# ioboard.net
KiCad netlist of a schematic drawn in EAGLE
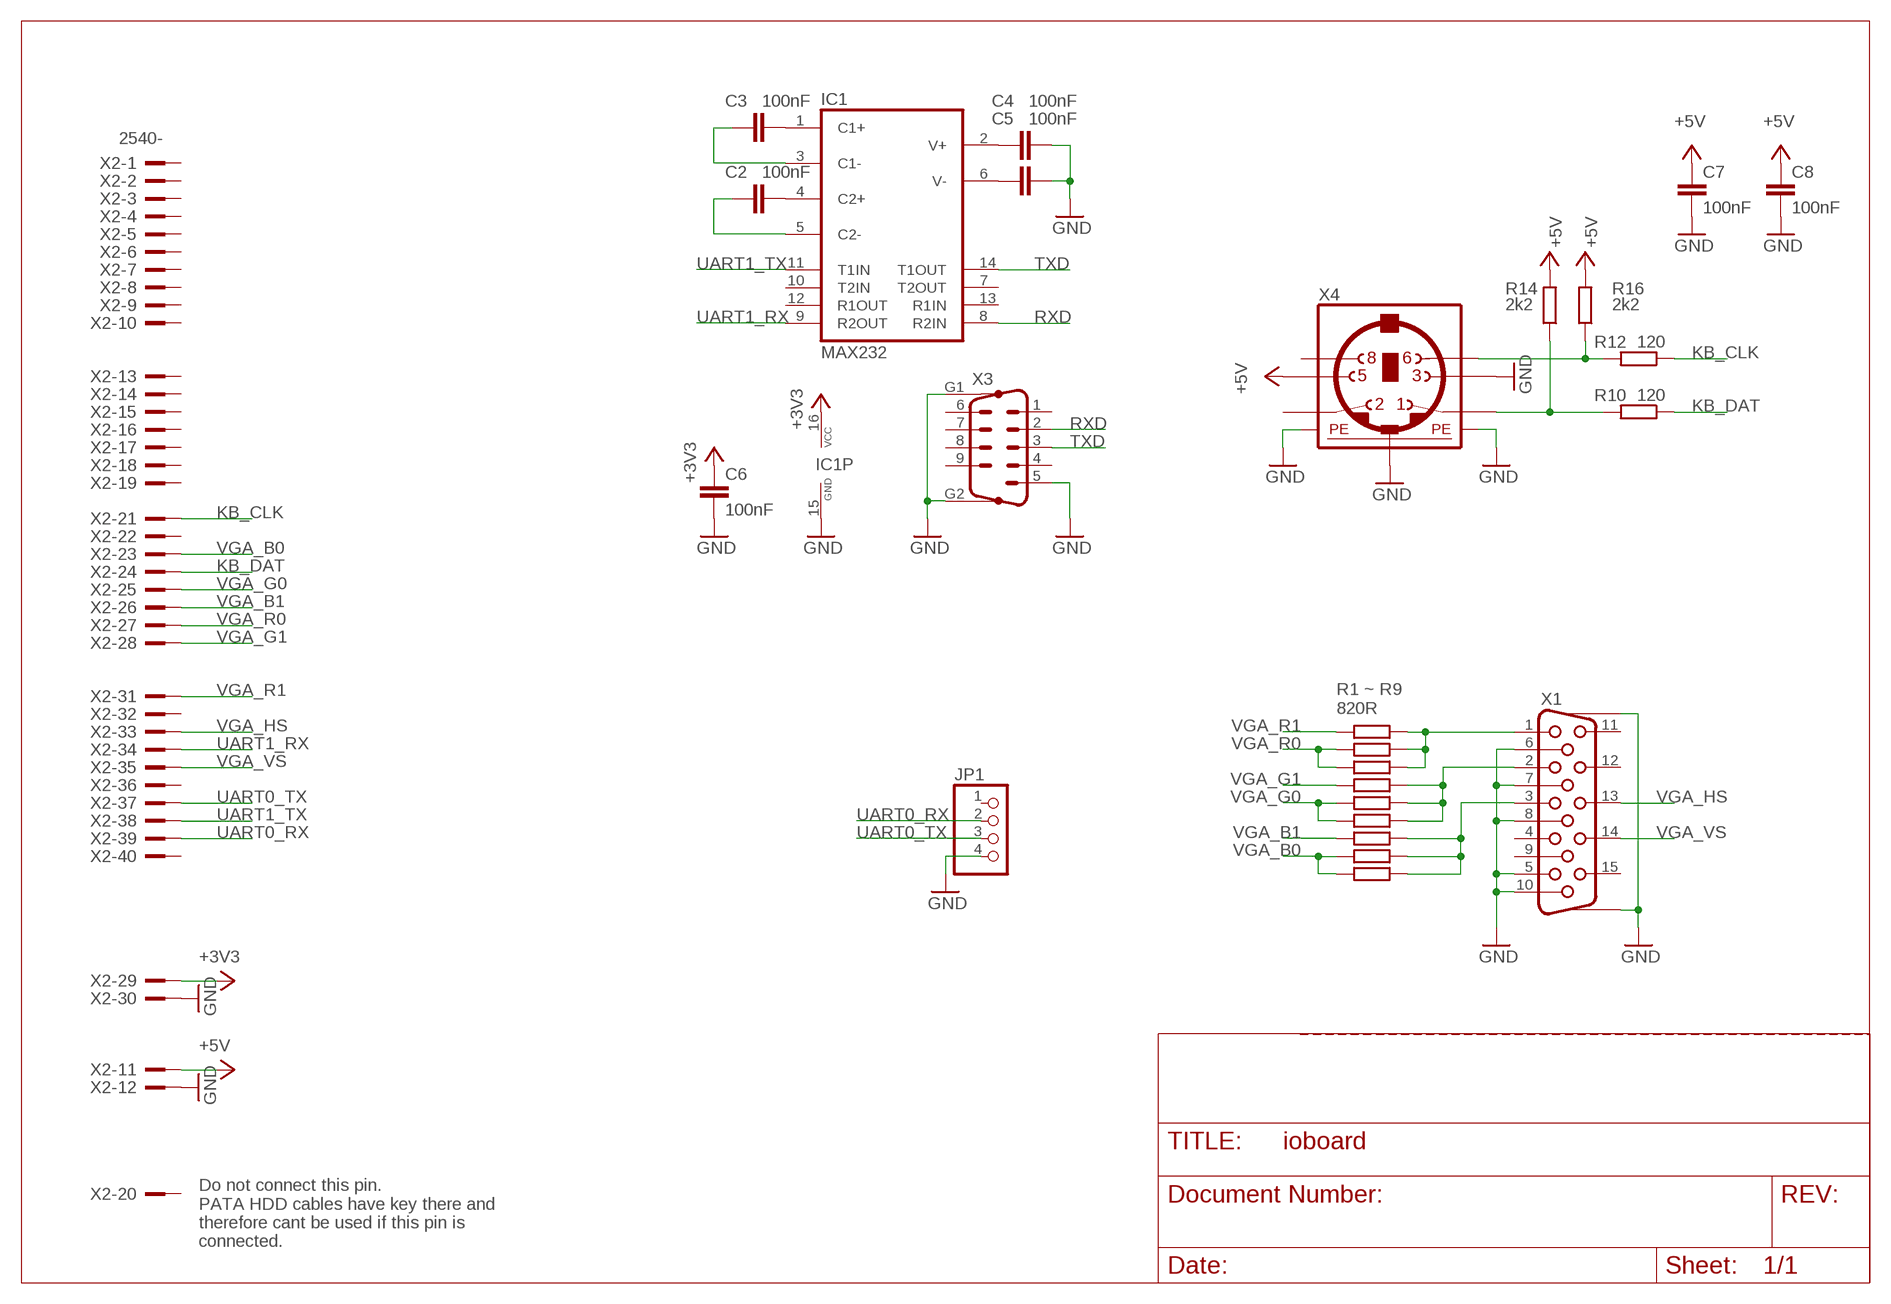
[diagram p0: schematic, sheet 1]

(export (version "E")
  (design (tool "Eeschema 10.0.6"))
  (components
    (comp (ref "C2")
      (value "100nF")
      (footprint "eagle-import:C025-025X050")
      (libsource (lib "eagle-import") (part "C-EU025-025X050"))
    )
    (comp (ref "C3")
      (value "100nF")
      (footprint "eagle-import:C025-025X050")
      (libsource (lib "eagle-import") (part "C-EU025-025X050"))
    )
    (comp (ref "C4")
      (value "100nF")
      (footprint "eagle-import:C025-025X050")
      (libsource (lib "eagle-import") (part "C-EU025-025X050"))
    )
    (comp (ref "C5")
      (value "100nF")
      (footprint "eagle-import:C025-025X050")
      (libsource (lib "eagle-import") (part "C-EU025-025X050"))
    )
    (comp (ref "C6")
      (value "100nF")
      (footprint "eagle-import:C025-025X050")
      (libsource (lib "eagle-import") (part "C-EU025-025X050"))
    )
    (comp (ref "C7")
      (value "100nF")
      (footprint "eagle-import:C025-025X050")
      (libsource (lib "eagle-import") (part "C-EU025-025X050"))
    )
    (comp (ref "C8")
      (value "100nF")
      (footprint "eagle-import:C025-025X050")
      (libsource (lib "eagle-import") (part "C-EU025-025X050"))
    )
    (comp (ref "IC1")
      (value "MAX232")
      (footprint "eagle-import:DIL16")
      (fields (field (name "MF") "MAXIM") (field (name "MPN") "MAX232ACPE+"))
      (libsource (lib "eagle-import") (part "MAX232"))
    )
    (comp (ref "JP1")
      (value "PINHD-1X4")
      (footprint "eagle-import:1X04")
      (libsource (lib "eagle-import") (part "PINHD-1X4"))
    )
    (comp (ref "R1")
      (value "820")
      (footprint "eagle-import:0204_7")
      (libsource (lib "eagle-import") (part "R-EU_0204/7"))
    )
    (comp (ref "R2")
      (value "820")
      (footprint "eagle-import:0204_7")
      (libsource (lib "eagle-import") (part "R-EU_0204/7"))
    )
    (comp (ref "R3")
      (value "820")
      (footprint "eagle-import:0204_7")
      (libsource (lib "eagle-import") (part "R-EU_0204/7"))
    )
    (comp (ref "R4")
      (value "820")
      (footprint "eagle-import:0204_7")
      (libsource (lib "eagle-import") (part "R-EU_0204/7"))
    )
    (comp (ref "R5")
      (value "820")
      (footprint "eagle-import:0204_7")
      (libsource (lib "eagle-import") (part "R-EU_0204/7"))
    )
    (comp (ref "R6")
      (value "820")
      (footprint "eagle-import:0204_7")
      (libsource (lib "eagle-import") (part "R-EU_0204/7"))
    )
    (comp (ref "R7")
      (value "820")
      (footprint "eagle-import:0204_7")
      (libsource (lib "eagle-import") (part "R-EU_0204/7"))
    )
    (comp (ref "R8")
      (value "820")
      (footprint "eagle-import:0204_7")
      (libsource (lib "eagle-import") (part "R-EU_0204/7"))
    )
    (comp (ref "R9")
      (value "820")
      (footprint "eagle-import:0204_7")
      (libsource (lib "eagle-import") (part "R-EU_0204/7"))
    )
    (comp (ref "R10")
      (value "120")
      (footprint "eagle-import:0204_7")
      (libsource (lib "eagle-import") (part "R-EU_0204/7"))
    )
    (comp (ref "R12")
      (value "120")
      (footprint "eagle-import:0204_7")
      (libsource (lib "eagle-import") (part "R-EU_0204/7"))
    )
    (comp (ref "R14")
      (value "2k2")
      (footprint "eagle-import:0204_7")
      (libsource (lib "eagle-import") (part "R-EU_0204/7"))
    )
    (comp (ref "R16")
      (value "2k2")
      (footprint "eagle-import:0204_7")
      (libsource (lib "eagle-import") (part "R-EU_0204/7"))
    )
    (comp (ref "X1")
      (value "HF15H")
      (footprint "eagle-import:HDF15H")
      (libsource (lib "eagle-import") (part "HF15H"))
    )
    (comp (ref "X2")
      (value "2540-")
      (footprint "eagle-import:PAK100_2500-40")
      (libsource (lib "eagle-import") (part "2540-"))
    )
    (comp (ref "X3")
      (value "M09HP")
      (footprint "eagle-import:M09HP")
      (libsource (lib "eagle-import") (part "M09HP"))
    )
    (comp (ref "X4")
      (value "MINI_DIN_6")
      (footprint "eagle-import:M_DIN6")
      (libsource (lib "eagle-import") (part "MINI_DIN_6"))
    )
  )
  (nets
    (net (code "1") (name "+3V3") (class "Default")
      (node (ref "C6") (pin "1") (pinfunction "1_1") (pintype "passive"))
      (node (ref "IC1") (pin "16") (pinfunction "VCC_16") (pintype "power_in"))
      (node (ref "X2") (pin "29") (pinfunction "KL_29") (pintype "passive"))
    )
    (net (code "2") (name "+5V") (class "Default")
      (node (ref "C7") (pin "1") (pinfunction "1_1") (pintype "passive"))
      (node (ref "C8") (pin "1") (pinfunction "1_1") (pintype "passive"))
      (node (ref "R14") (pin "2") (pinfunction "2_2") (pintype "passive"))
      (node (ref "R16") (pin "2") (pinfunction "2_2") (pintype "passive"))
      (node (ref "X2") (pin "11") (pinfunction "KL_11") (pintype "passive"))
      (node (ref "X4") (pin "5") (pinfunction "5_5") (pintype "passive"))
    )
    (net (code "3") (name "/KB_CLK") (class "Default")
      (node (ref "R12") (pin "1") (pinfunction "1_1") (pintype "passive"))
      (node (ref "X2") (pin "21") (pinfunction "KL_21") (pintype "passive"))
    )
    (net (code "4") (name "/KB_DAT") (class "Default")
      (node (ref "R10") (pin "1") (pinfunction "1_1") (pintype "passive"))
      (node (ref "X2") (pin "24") (pinfunction "KL_24") (pintype "passive"))
    )
    (net (code "5") (name "/RXD") (class "Default")
      (node (ref "IC1") (pin "8") (pinfunction "R2IN_8") (pintype "input"))
      (node (ref "X3") (pin "2") (pinfunction "2_2") (pintype "passive"))
    )
    (net (code "6") (name "/TXD") (class "Default")
      (node (ref "IC1") (pin "14") (pinfunction "T1OUT_14") (pintype "output"))
      (node (ref "X3") (pin "3") (pinfunction "3_3") (pintype "passive"))
    )
    (net (code "7") (name "/UART0_RX") (class "Default")
      (node (ref "JP1") (pin "2") (pinfunction "2_2") (pintype "passive"))
      (node (ref "X2") (pin "39") (pinfunction "KL_39") (pintype "passive"))
    )
    (net (code "8") (name "/UART0_TX") (class "Default")
      (node (ref "JP1") (pin "3") (pinfunction "3_3") (pintype "passive"))
      (node (ref "X2") (pin "37") (pinfunction "KL_37") (pintype "passive"))
    )
    (net (code "9") (name "/UART1_RX") (class "Default")
      (node (ref "IC1") (pin "9") (pinfunction "R2OUT_9") (pintype "output"))
      (node (ref "X2") (pin "34") (pinfunction "KL_34") (pintype "passive"))
    )
    (net (code "10") (name "/UART1_TX") (class "Default")
      (node (ref "IC1") (pin "11") (pinfunction "T1IN_11") (pintype "input"))
      (node (ref "X2") (pin "38") (pinfunction "KL_38") (pintype "passive"))
    )
    (net (code "11") (name "/VGA_B0") (class "Default")
      (node (ref "R8") (pin "2") (pinfunction "2_2") (pintype "passive"))
      (node (ref "R9") (pin "2") (pinfunction "2_2") (pintype "passive"))
      (node (ref "X2") (pin "23") (pinfunction "KL_23") (pintype "passive"))
    )
    (net (code "12") (name "/VGA_B1") (class "Default")
      (node (ref "R7") (pin "2") (pinfunction "2_2") (pintype "passive"))
      (node (ref "X2") (pin "26") (pinfunction "KL_26") (pintype "passive"))
    )
    (net (code "13") (name "/VGA_G0") (class "Default")
      (node (ref "R5") (pin "2") (pinfunction "2_2") (pintype "passive"))
      (node (ref "R6") (pin "2") (pinfunction "2_2") (pintype "passive"))
      (node (ref "X2") (pin "25") (pinfunction "KL_25") (pintype "passive"))
    )
    (net (code "14") (name "/VGA_G1") (class "Default")
      (node (ref "R4") (pin "2") (pinfunction "2_2") (pintype "passive"))
      (node (ref "X2") (pin "28") (pinfunction "KL_28") (pintype "passive"))
    )
    (net (code "15") (name "/VGA_HS") (class "Default")
      (node (ref "X1") (pin "13") (pinfunction "13_13") (pintype "passive"))
      (node (ref "X2") (pin "33") (pinfunction "KL_33") (pintype "passive"))
    )
    (net (code "16") (name "/VGA_R0") (class "Default")
      (node (ref "R2") (pin "2") (pinfunction "2_2") (pintype "passive"))
      (node (ref "R3") (pin "2") (pinfunction "2_2") (pintype "passive"))
      (node (ref "X2") (pin "27") (pinfunction "KL_27") (pintype "passive"))
    )
    (net (code "17") (name "/VGA_R1") (class "Default")
      (node (ref "R1") (pin "2") (pinfunction "2_2") (pintype "passive"))
      (node (ref "X2") (pin "31") (pinfunction "KL_31") (pintype "passive"))
    )
    (net (code "18") (name "/VGA_VS") (class "Default")
      (node (ref "X1") (pin "14") (pinfunction "14_14") (pintype "passive"))
      (node (ref "X2") (pin "35") (pinfunction "KL_35") (pintype "passive"))
    )
    (net (code "19") (name "GND") (class "Default")
      (node (ref "C4") (pin "2") (pinfunction "2_2") (pintype "passive"))
      (node (ref "C5") (pin "2") (pinfunction "2_2") (pintype "passive"))
      (node (ref "C6") (pin "2") (pinfunction "2_2") (pintype "passive"))
      (node (ref "C7") (pin "2") (pinfunction "2_2") (pintype "passive"))
      (node (ref "C8") (pin "2") (pinfunction "2_2") (pintype "passive"))
      (node (ref "IC1") (pin "15") (pinfunction "GND_15") (pintype "power_in"))
      (node (ref "JP1") (pin "4") (pinfunction "4_4") (pintype "passive"))
      (node (ref "X1") (pin "10") (pinfunction "10_10") (pintype "passive"))
      (node (ref "X1") (pin "5") (pinfunction "5_5") (pintype "passive"))
      (node (ref "X1") (pin "6") (pinfunction "6_6") (pintype "passive"))
      (node (ref "X1") (pin "7") (pinfunction "7_7") (pintype "passive"))
      (node (ref "X1") (pin "8") (pinfunction "8_8") (pintype "passive"))
      (node (ref "X1") (pin "SCH1") (pinfunction "P$1_SCH1") (pintype "passive"))
      (node (ref "X1") (pin "SCH2") (pinfunction "P$2_SCH2") (pintype "passive"))
      (node (ref "X2") (pin "12") (pinfunction "KL_12") (pintype "passive"))
      (node (ref "X2") (pin "30") (pinfunction "KL_30") (pintype "passive"))
      (node (ref "X3") (pin "5") (pinfunction "5_5") (pintype "passive"))
      (node (ref "X3") (pin "G1") (pinfunction "G1_G1") (pintype "passive"))
      (node (ref "X3") (pin "G2") (pinfunction "G2_G2") (pintype "passive"))
      (node (ref "X4") (pin "3") (pinfunction "3_3") (pintype "passive"))
      (node (ref "X4") (pin "SH1") (pinfunction "PE1_SH1") (pintype "power_in"))
      (node (ref "X4") (pin "SH2") (pinfunction "PE2_SH2") (pintype "power_in"))
      (node (ref "X4") (pin "SH3") (pinfunction "PE3_SH3") (pintype "power_in"))
    )
    (net (code "20") (name "Net-(IC1A-C1+)") (class "Default")
      (node (ref "C3") (pin "2") (pinfunction "2_2") (pintype "passive"))
      (node (ref "IC1") (pin "1") (pinfunction "C1+_1") (pintype "bidirectional"))
    )
    (net (code "21") (name "Net-(IC1A-C1-)") (class "Default")
      (node (ref "C3") (pin "1") (pinfunction "1_1") (pintype "passive"))
      (node (ref "IC1") (pin "3") (pinfunction "C1-_3") (pintype "bidirectional"))
    )
    (net (code "22") (name "Net-(IC1A-C2+)") (class "Default")
      (node (ref "C2") (pin "2") (pinfunction "2_2") (pintype "passive"))
      (node (ref "IC1") (pin "4") (pinfunction "C2+_4") (pintype "bidirectional"))
    )
    (net (code "23") (name "Net-(IC1A-C2-)") (class "Default")
      (node (ref "C2") (pin "1") (pinfunction "1_1") (pintype "passive"))
      (node (ref "IC1") (pin "5") (pinfunction "C2-_5") (pintype "bidirectional"))
    )
    (net (code "24") (name "Net-(IC1A-V+)") (class "Default")
      (node (ref "C4") (pin "1") (pinfunction "1_1") (pintype "passive"))
      (node (ref "IC1") (pin "2") (pinfunction "V+_2") (pintype "bidirectional"))
    )
    (net (code "25") (name "Net-(IC1A-V-)") (class "Default")
      (node (ref "C5") (pin "1") (pinfunction "1_1") (pintype "passive"))
      (node (ref "IC1") (pin "6") (pinfunction "V-_6") (pintype "bidirectional"))
    )
    (net (code "26") (name "Net-(R1-Pad1)") (class "Default")
      (node (ref "R1") (pin "1") (pinfunction "1_1") (pintype "passive"))
      (node (ref "R2") (pin "1") (pinfunction "1_1") (pintype "passive"))
      (node (ref "R3") (pin "1") (pinfunction "1_1") (pintype "passive"))
      (node (ref "X1") (pin "1") (pinfunction "1_1") (pintype "passive"))
    )
    (net (code "27") (name "Net-(R4-Pad1)") (class "Default")
      (node (ref "R4") (pin "1") (pinfunction "1_1") (pintype "passive"))
      (node (ref "R5") (pin "1") (pinfunction "1_1") (pintype "passive"))
      (node (ref "R6") (pin "1") (pinfunction "1_1") (pintype "passive"))
      (node (ref "X1") (pin "2") (pinfunction "2_2") (pintype "passive"))
    )
    (net (code "28") (name "Net-(R7-Pad1)") (class "Default")
      (node (ref "R7") (pin "1") (pinfunction "1_1") (pintype "passive"))
      (node (ref "R8") (pin "1") (pinfunction "1_1") (pintype "passive"))
      (node (ref "R9") (pin "1") (pinfunction "1_1") (pintype "passive"))
      (node (ref "X1") (pin "3") (pinfunction "3_3") (pintype "passive"))
    )
    (net (code "29") (name "Net-(R10-Pad2)") (class "Default")
      (node (ref "R10") (pin "2") (pinfunction "2_2") (pintype "passive"))
      (node (ref "R14") (pin "1") (pinfunction "1_1") (pintype "passive"))
      (node (ref "X4") (pin "1") (pinfunction "1_1") (pintype "passive"))
    )
    (net (code "30") (name "Net-(R12-Pad2)") (class "Default")
      (node (ref "R12") (pin "2") (pinfunction "2_2") (pintype "passive"))
      (node (ref "R16") (pin "1") (pinfunction "1_1") (pintype "passive"))
      (node (ref "X4") (pin "6") (pinfunction "6_6") (pintype "passive"))
    )
    (net (code "31") (name "unconnected-(IC1A-R1IN-Pad13)") (class "Default")
      (node (ref "IC1") (pin "13") (pinfunction "R1IN_13") (pintype "input"))
    )
    (net (code "32") (name "unconnected-(IC1A-R1OUT-Pad12)") (class "Default")
      (node (ref "IC1") (pin "12") (pinfunction "R1OUT_12") (pintype "output"))
    )
    (net (code "33") (name "unconnected-(IC1A-T2IN-Pad10)") (class "Default")
      (node (ref "IC1") (pin "10") (pinfunction "T2IN_10") (pintype "input"))
    )
    (net (code "34") (name "unconnected-(IC1A-T2OUT-Pad7)") (class "Default")
      (node (ref "IC1") (pin "7") (pinfunction "T2OUT_7") (pintype "output"))
    )
    (net (code "35") (name "unconnected-(JP1-Pad1)") (class "Default")
      (node (ref "JP1") (pin "1") (pinfunction "1_1") (pintype "passive"))
    )
    (net (code "36") (name "unconnected-(X1-Pad4)") (class "Default")
      (node (ref "X1") (pin "4") (pinfunction "4_4") (pintype "passive"))
    )
    (net (code "37") (name "unconnected-(X1-Pad9)") (class "Default")
      (node (ref "X1") (pin "9") (pinfunction "9_9") (pintype "passive"))
    )
    (net (code "38") (name "unconnected-(X1-Pad11)") (class "Default")
      (node (ref "X1") (pin "11") (pinfunction "11_11") (pintype "passive"))
    )
    (net (code "39") (name "unconnected-(X1-Pad12)") (class "Default")
      (node (ref "X1") (pin "12") (pinfunction "12_12") (pintype "passive"))
    )
    (net (code "40") (name "unconnected-(X1-Pad15)") (class "Default")
      (node (ref "X1") (pin "15") (pinfunction "15_15") (pintype "passive"))
    )
    (net (code "41") (name "unconnected-(X2A-KL-Pad1)") (class "Default")
      (node (ref "X2") (pin "1") (pinfunction "KL_1") (pintype "passive"))
    )
    (net (code "42") (name "unconnected-(X2AD-KL-Pad36)") (class "Default")
      (node (ref "X2") (pin "36") (pinfunction "KL_36") (pintype "passive"))
    )
    (net (code "43") (name "unconnected-(X2AH-KL-Pad4)") (class "Default")
      (node (ref "X2") (pin "4") (pinfunction "KL_4") (pintype "passive"))
    )
    (net (code "44") (name "unconnected-(X2AI-KL-Pad40)") (class "Default")
      (node (ref "X2") (pin "40") (pinfunction "KL_40") (pintype "passive"))
    )
    (net (code "45") (name "unconnected-(X2AJ-KL-Pad5)") (class "Default")
      (node (ref "X2") (pin "5") (pinfunction "KL_5") (pintype "passive"))
    )
    (net (code "46") (name "unconnected-(X2AK-KL-Pad6)") (class "Default")
      (node (ref "X2") (pin "6") (pinfunction "KL_6") (pintype "passive"))
    )
    (net (code "47") (name "unconnected-(X2AL-KL-Pad7)") (class "Default")
      (node (ref "X2") (pin "7") (pinfunction "KL_7") (pintype "passive"))
    )
    (net (code "48") (name "unconnected-(X2AM-KL-Pad8)") (class "Default")
      (node (ref "X2") (pin "8") (pinfunction "KL_8") (pintype "passive"))
    )
    (net (code "49") (name "unconnected-(X2AN-KL-Pad9)") (class "Default")
      (node (ref "X2") (pin "9") (pinfunction "KL_9") (pintype "passive"))
    )
    (net (code "50") (name "unconnected-(X2B-KL-Pad10)") (class "Default")
      (node (ref "X2") (pin "10") (pinfunction "KL_10") (pintype "passive"))
    )
    (net (code "51") (name "unconnected-(X2E-KL-Pad13)") (class "Default")
      (node (ref "X2") (pin "13") (pinfunction "KL_13") (pintype "passive"))
    )
    (net (code "52") (name "unconnected-(X2F-KL-Pad14)") (class "Default")
      (node (ref "X2") (pin "14") (pinfunction "KL_14") (pintype "passive"))
    )
    (net (code "53") (name "unconnected-(X2G-KL-Pad15)") (class "Default")
      (node (ref "X2") (pin "15") (pinfunction "KL_15") (pintype "passive"))
    )
    (net (code "54") (name "unconnected-(X2H-KL-Pad16)") (class "Default")
      (node (ref "X2") (pin "16") (pinfunction "KL_16") (pintype "passive"))
    )
    (net (code "55") (name "unconnected-(X2I-KL-Pad17)") (class "Default")
      (node (ref "X2") (pin "17") (pinfunction "KL_17") (pintype "passive"))
    )
    (net (code "56") (name "unconnected-(X2J-KL-Pad18)") (class "Default")
      (node (ref "X2") (pin "18") (pinfunction "KL_18") (pintype "passive"))
    )
    (net (code "57") (name "unconnected-(X2K-KL-Pad19)") (class "Default")
      (node (ref "X2") (pin "19") (pinfunction "KL_19") (pintype "passive"))
    )
    (net (code "58") (name "unconnected-(X2L-KL-Pad2)") (class "Default")
      (node (ref "X2") (pin "2") (pinfunction "KL_2") (pintype "passive"))
    )
    (net (code "59") (name "unconnected-(X2M-KL-Pad20)") (class "Default")
      (node (ref "X2") (pin "20") (pinfunction "KL_20") (pintype "passive"))
    )
    (net (code "60") (name "unconnected-(X2O-KL-Pad22)") (class "Default")
      (node (ref "X2") (pin "22") (pinfunction "KL_22") (pintype "passive"))
    )
    (net (code "61") (name "unconnected-(X2W-KL-Pad3)") (class "Default")
      (node (ref "X2") (pin "3") (pinfunction "KL_3") (pintype "passive"))
    )
    (net (code "62") (name "unconnected-(X2Z-KL-Pad32)") (class "Default")
      (node (ref "X2") (pin "32") (pinfunction "KL_32") (pintype "passive"))
    )
    (net (code "63") (name "unconnected-(X3-Pad1)") (class "Default")
      (node (ref "X3") (pin "1") (pinfunction "1_1") (pintype "passive"))
    )
    (net (code "64") (name "unconnected-(X3-Pad4)") (class "Default")
      (node (ref "X3") (pin "4") (pinfunction "4_4") (pintype "passive"))
    )
    (net (code "65") (name "unconnected-(X3-Pad6)") (class "Default")
      (node (ref "X3") (pin "6") (pinfunction "6_6") (pintype "passive"))
    )
    (net (code "66") (name "unconnected-(X3-Pad7)") (class "Default")
      (node (ref "X3") (pin "7") (pinfunction "7_7") (pintype "passive"))
    )
    (net (code "67") (name "unconnected-(X3-Pad8)") (class "Default")
      (node (ref "X3") (pin "8") (pinfunction "8_8") (pintype "passive"))
    )
    (net (code "68") (name "unconnected-(X3-Pad9)") (class "Default")
      (node (ref "X3") (pin "9") (pinfunction "9_9") (pintype "passive"))
    )
    (net (code "69") (name "unconnected-(X4-Pad2)") (class "Default")
      (node (ref "X4") (pin "2") (pinfunction "2_2") (pintype "passive"))
    )
    (net (code "70") (name "unconnected-(X4-Pad8)") (class "Default")
      (node (ref "X4") (pin "8") (pinfunction "8_8") (pintype "passive"))
    )
  )
)
